# HorusBoard.net
KiCad netlist of a schematic drawn in EAGLE
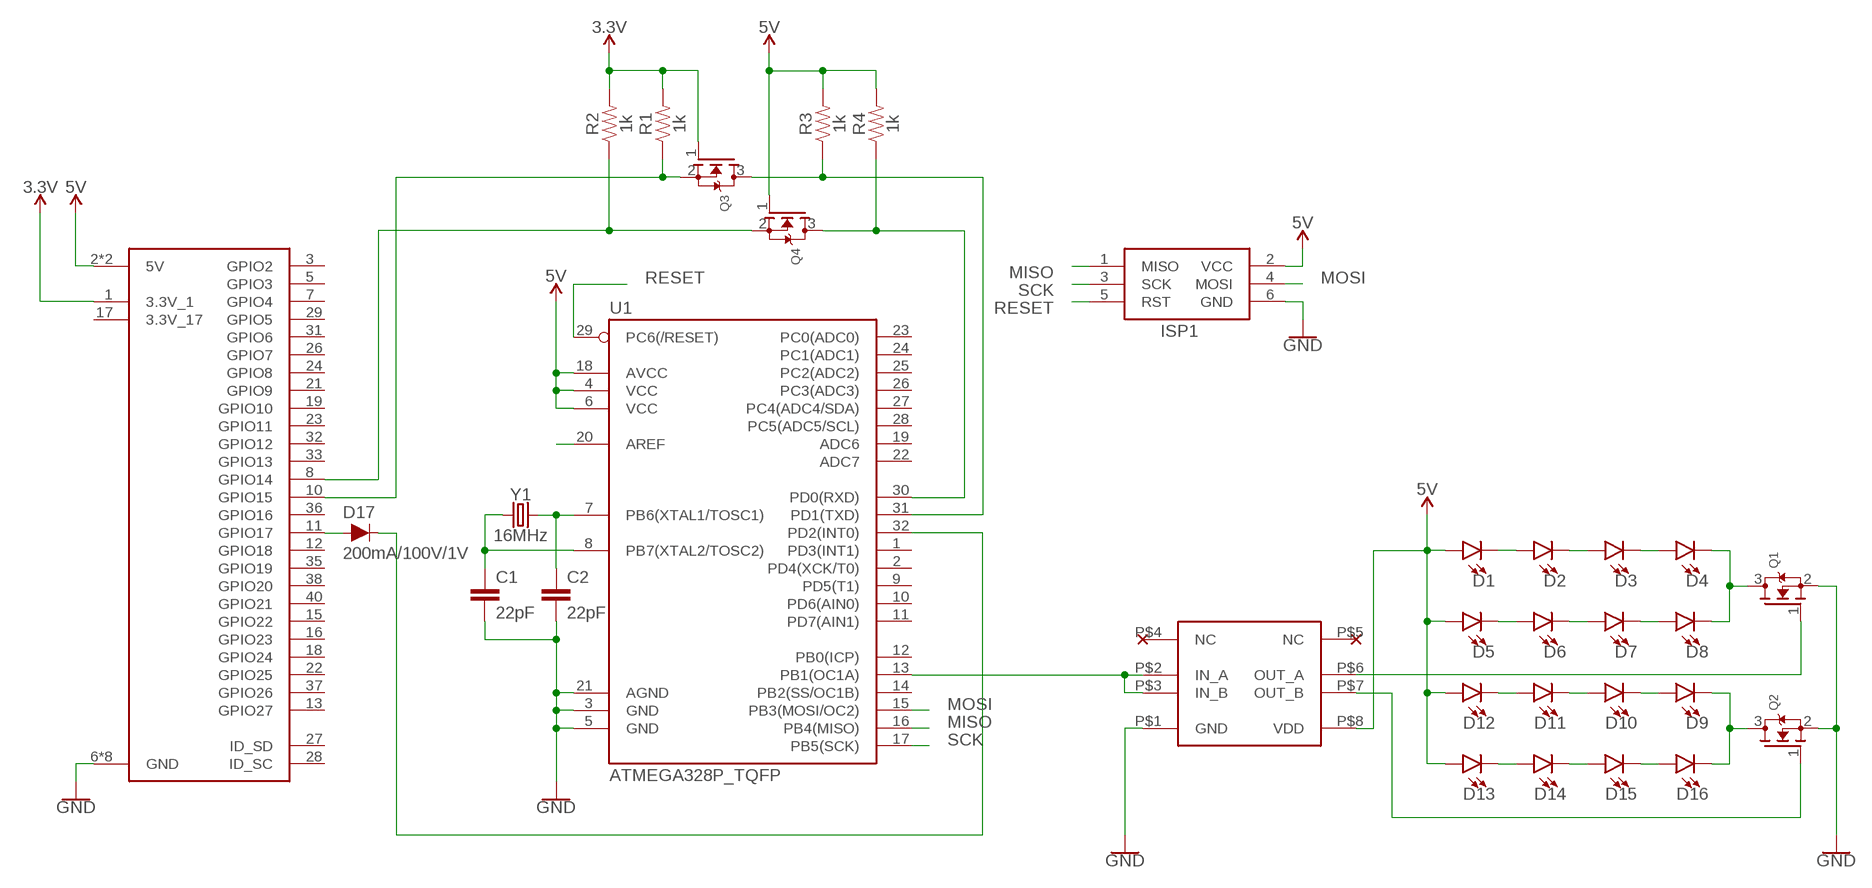
[diagram p0: schematic, sheet 1]

(export (version "E")
  (design (tool "Eeschema 10.0.6"))
  (components
    (comp (ref "C1")
      (value "22pF")
      (footprint "eagle-import:0603")
      (libsource (lib "eagle-import") (part "22PF-0603-50V-5%"))
    )
    (comp (ref "C2")
      (value "22pF")
      (footprint "eagle-import:0603")
      (libsource (lib "eagle-import") (part "22PF-0603-50V-5%"))
    )
    (comp (ref "D1")
      (value "LED3MM")
      (footprint "eagle-import:LED_3MM")
      (libsource (lib "eagle-import") (part "LED3MM"))
    )
    (comp (ref "D2")
      (value "LED3MM")
      (footprint "eagle-import:LED_3MM")
      (libsource (lib "eagle-import") (part "LED3MM"))
    )
    (comp (ref "D3")
      (value "LED3MM")
      (footprint "eagle-import:LED_3MM")
      (libsource (lib "eagle-import") (part "LED3MM"))
    )
    (comp (ref "D4")
      (value "LED3MM")
      (footprint "eagle-import:LED_3MM")
      (libsource (lib "eagle-import") (part "LED3MM"))
    )
    (comp (ref "D5")
      (value "LED3MM")
      (footprint "eagle-import:LED_3MM")
      (libsource (lib "eagle-import") (part "LED3MM"))
    )
    (comp (ref "D6")
      (value "LED3MM")
      (footprint "eagle-import:LED_3MM")
      (libsource (lib "eagle-import") (part "LED3MM"))
    )
    (comp (ref "D7")
      (value "LED3MM")
      (footprint "eagle-import:LED_3MM")
      (libsource (lib "eagle-import") (part "LED3MM"))
    )
    (comp (ref "D8")
      (value "LED3MM")
      (footprint "eagle-import:LED_3MM")
      (libsource (lib "eagle-import") (part "LED3MM"))
    )
    (comp (ref "D9")
      (value "LED3MM")
      (footprint "eagle-import:LED_3MM")
      (libsource (lib "eagle-import") (part "LED3MM"))
    )
    (comp (ref "D10")
      (value "LED3MM")
      (footprint "eagle-import:LED_3MM")
      (libsource (lib "eagle-import") (part "LED3MM"))
    )
    (comp (ref "D11")
      (value "LED3MM")
      (footprint "eagle-import:LED_3MM")
      (libsource (lib "eagle-import") (part "LED3MM"))
    )
    (comp (ref "D12")
      (value "LED3MM")
      (footprint "eagle-import:LED_3MM")
      (libsource (lib "eagle-import") (part "LED3MM"))
    )
    (comp (ref "D13")
      (value "LED3MM")
      (footprint "eagle-import:LED_3MM")
      (libsource (lib "eagle-import") (part "LED3MM"))
    )
    (comp (ref "D14")
      (value "LED3MM")
      (footprint "eagle-import:LED_3MM")
      (libsource (lib "eagle-import") (part "LED3MM"))
    )
    (comp (ref "D15")
      (value "LED3MM")
      (footprint "eagle-import:LED_3MM")
      (libsource (lib "eagle-import") (part "LED3MM"))
    )
    (comp (ref "D16")
      (value "LED3MM")
      (footprint "eagle-import:LED_3MM")
      (libsource (lib "eagle-import") (part "LED3MM"))
    )
    (comp (ref "D17")
      (value "200mA/100V/1V")
      (footprint "eagle-import:DIODE-1N4148")
      (libsource (lib "eagle-import") (part "DIODE-1N4148"))
    )
    (comp (ref "ISP1")
      (value "AVRISP-6")
      (footprint "eagle-import:AVRISP")
      (libsource (lib "eagle-import") (part "AVRISP-6"))
    )
    (comp (ref "Q1")
      (value "MOSFET-NREFLOW")
      (footprint "eagle-import:SOT23")
      (libsource (lib "eagle-import") (part "MOSFET-NREFLOW"))
    )
    (comp (ref "Q2")
      (value "MOSFET-NREFLOW")
      (footprint "eagle-import:SOT23")
      (libsource (lib "eagle-import") (part "MOSFET-NREFLOW"))
    )
    (comp (ref "Q3")
      (value "MOSFET-NREFLOW")
      (footprint "eagle-import:SOT23")
      (libsource (lib "eagle-import") (part "MOSFET-NREFLOW"))
    )
    (comp (ref "Q4")
      (value "MOSFET-NREFLOW")
      (footprint "eagle-import:SOT23")
      (libsource (lib "eagle-import") (part "MOSFET-NREFLOW"))
    )
    (comp (ref "R1")
      (value "1k")
      (footprint "eagle-import:AXIAL-0.3")
      (libsource (lib "eagle-import") (part "1KOHM-HORIZ-1/4W-5%"))
    )
    (comp (ref "R2")
      (value "1k")
      (footprint "eagle-import:AXIAL-0.3")
      (libsource (lib "eagle-import") (part "1KOHM-HORIZ-1/4W-5%"))
    )
    (comp (ref "R3")
      (value "1k")
      (footprint "eagle-import:AXIAL-0.3")
      (libsource (lib "eagle-import") (part "1KOHM-HORIZ-1/4W-5%"))
    )
    (comp (ref "R4")
      (value "1k")
      (footprint "eagle-import:AXIAL-0.3")
      (libsource (lib "eagle-import") (part "1KOHM-HORIZ-1/4W-5%"))
    )
    (comp (ref "U$1")
      (value "TC4427")
      (footprint "eagle-import:8-SOIC")
      (libsource (lib "eagle-import") (part "TC4427"))
    )
    (comp (ref "U$2")
      (value "RASPBERRY_PI_3")
      (footprint "eagle-import:RASPBERRY_PI_3")
      (libsource (lib "eagle-import") (part "RASPBERRY_PI_3"))
    )
    (comp (ref "U1")
      (value "ATMEGA328P_TQFP")
      (footprint "eagle-import:TQFP32-08")
      (libsource (lib "eagle-import") (part "ATMEGA328P_TQFP"))
    )
    (comp (ref "Y1")
      (value "16MHz")
      (footprint "eagle-import:HC49US")
      (libsource (lib "eagle-import") (part "CRYSTAL-16MHZPTH-HC49US"))
    )
  )
  (nets
    (net (code "1") (name "/MISO") (class "Default")
      (node (ref "ISP1") (pin "1") (pinfunction "MISO_1") (pintype "input"))
      (node (ref "U1") (pin "16") (pinfunction "PB4(MISO)_16") (pintype "bidirectional"))
    )
    (net (code "2") (name "/MOSI") (class "Default")
      (node (ref "ISP1") (pin "4") (pinfunction "MOSI_4") (pintype "output"))
      (node (ref "U1") (pin "15") (pinfunction "PB3(MOSI/OC2)_15") (pintype "bidirectional"))
    )
    (net (code "3") (name "/RESET") (class "Default")
      (node (ref "ISP1") (pin "5") (pinfunction "RST_5") (pintype "output"))
      (node (ref "U1") (pin "29") (pinfunction "PC6(/RESET)_29") (pintype "bidirectional"))
    )
    (net (code "4") (name "/SCK") (class "Default")
      (node (ref "ISP1") (pin "3") (pinfunction "SCK_3") (pintype "output"))
      (node (ref "U1") (pin "17") (pinfunction "PB5(SCK)_17") (pintype "bidirectional"))
    )
    (net (code "5") (name "3.3V") (class "Default")
      (node (ref "Q3") (pin "1") (pinfunction "G_1") (pintype "bidirectional"))
      (node (ref "R1") (pin "P$2") (pinfunction "2_P$2") (pintype "passive"))
      (node (ref "R2") (pin "P$2") (pinfunction "2_P$2") (pintype "passive"))
      (node (ref "U$2") (pin "1") (pinfunction "3.3V_1_1") (pintype "bidirectional"))
    )
    (net (code "6") (name "5V") (class "Default")
      (node (ref "D1") (pin "A") (pinfunction "A_A") (pintype "passive"))
      (node (ref "D12") (pin "A") (pinfunction "A_A") (pintype "passive"))
      (node (ref "D13") (pin "A") (pinfunction "A_A") (pintype "passive"))
      (node (ref "D5") (pin "A") (pinfunction "A_A") (pintype "passive"))
      (node (ref "ISP1") (pin "2") (pinfunction "VCC_2") (pintype "power_in"))
      (node (ref "Q4") (pin "1") (pinfunction "G_1") (pintype "bidirectional"))
      (node (ref "R3") (pin "P$2") (pinfunction "2_P$2") (pintype "passive"))
      (node (ref "R4") (pin "P$2") (pinfunction "2_P$2") (pintype "passive"))
      (node (ref "U$1") (pin "P$8") (pinfunction "VDD_P$8") (pintype "bidirectional"))
      (node (ref "U$2") (pin "2") (pinfunction "5V_2") (pintype "bidirectional"))
      (node (ref "U$2") (pin "4") (pinfunction "5V_4") (pintype "bidirectional"))
      (node (ref "U1") (pin "18") (pinfunction "AVCC_18") (pintype "bidirectional"))
      (node (ref "U1") (pin "4") (pinfunction "VCC_4") (pintype "bidirectional"))
      (node (ref "U1") (pin "6") (pinfunction "VCC_6") (pintype "bidirectional"))
    )
    (net (code "7") (name "GND") (class "Default")
      (node (ref "C1") (pin "2") (pinfunction "2_2") (pintype "passive"))
      (node (ref "C2") (pin "2") (pinfunction "2_2") (pintype "passive"))
      (node (ref "ISP1") (pin "6") (pinfunction "GND_6") (pintype "power_in"))
      (node (ref "Q1") (pin "2") (pinfunction "S_2") (pintype "bidirectional"))
      (node (ref "Q2") (pin "2") (pinfunction "S_2") (pintype "bidirectional"))
      (node (ref "U$1") (pin "P$1") (pinfunction "GND_P$1") (pintype "bidirectional"))
      (node (ref "U$2") (pin "14") (pinfunction "GND_14") (pintype "bidirectional"))
      (node (ref "U$2") (pin "20") (pinfunction "GND_20") (pintype "bidirectional"))
      (node (ref "U$2") (pin "25") (pinfunction "GND_25") (pintype "bidirectional"))
      (node (ref "U$2") (pin "30") (pinfunction "GND_30") (pintype "bidirectional"))
      (node (ref "U$2") (pin "34") (pinfunction "GND_34") (pintype "bidirectional"))
      (node (ref "U$2") (pin "39") (pinfunction "GND_39") (pintype "bidirectional"))
      (node (ref "U$2") (pin "6") (pinfunction "GND_6") (pintype "bidirectional"))
      (node (ref "U$2") (pin "9") (pinfunction "GND_9") (pintype "bidirectional"))
      (node (ref "U1") (pin "21") (pinfunction "AGND_21") (pintype "bidirectional"))
      (node (ref "U1") (pin "3") (pinfunction "GND_3") (pintype "bidirectional"))
      (node (ref "U1") (pin "5") (pinfunction "GND_5") (pintype "bidirectional"))
    )
    (net (code "8") (name "Net-(D1-C)") (class "Default")
      (node (ref "D1") (pin "K") (pinfunction "C_K") (pintype "passive"))
      (node (ref "D2") (pin "A") (pinfunction "A_A") (pintype "passive"))
    )
    (net (code "9") (name "Net-(D2-C)") (class "Default")
      (node (ref "D2") (pin "K") (pinfunction "C_K") (pintype "passive"))
      (node (ref "D3") (pin "A") (pinfunction "A_A") (pintype "passive"))
    )
    (net (code "10") (name "Net-(D3-C)") (class "Default")
      (node (ref "D3") (pin "K") (pinfunction "C_K") (pintype "passive"))
      (node (ref "D4") (pin "A") (pinfunction "A_A") (pintype "passive"))
    )
    (net (code "11") (name "Net-(D4-C)") (class "Default")
      (node (ref "D4") (pin "K") (pinfunction "C_K") (pintype "passive"))
      (node (ref "D8") (pin "K") (pinfunction "C_K") (pintype "passive"))
      (node (ref "Q1") (pin "3") (pinfunction "D_3") (pintype "bidirectional"))
    )
    (net (code "12") (name "Net-(D5-C)") (class "Default")
      (node (ref "D5") (pin "K") (pinfunction "C_K") (pintype "passive"))
      (node (ref "D6") (pin "A") (pinfunction "A_A") (pintype "passive"))
    )
    (net (code "13") (name "Net-(D6-C)") (class "Default")
      (node (ref "D6") (pin "K") (pinfunction "C_K") (pintype "passive"))
      (node (ref "D7") (pin "A") (pinfunction "A_A") (pintype "passive"))
    )
    (net (code "14") (name "Net-(D7-C)") (class "Default")
      (node (ref "D7") (pin "K") (pinfunction "C_K") (pintype "passive"))
      (node (ref "D8") (pin "A") (pinfunction "A_A") (pintype "passive"))
    )
    (net (code "15") (name "Net-(D10-C)") (class "Default")
      (node (ref "D10") (pin "K") (pinfunction "C_K") (pintype "passive"))
      (node (ref "D9") (pin "A") (pinfunction "A_A") (pintype "passive"))
    )
    (net (code "16") (name "Net-(D11-C)") (class "Default")
      (node (ref "D10") (pin "A") (pinfunction "A_A") (pintype "passive"))
      (node (ref "D11") (pin "K") (pinfunction "C_K") (pintype "passive"))
    )
    (net (code "17") (name "Net-(D12-C)") (class "Default")
      (node (ref "D11") (pin "A") (pinfunction "A_A") (pintype "passive"))
      (node (ref "D12") (pin "K") (pinfunction "C_K") (pintype "passive"))
    )
    (net (code "18") (name "Net-(D13-C)") (class "Default")
      (node (ref "D13") (pin "K") (pinfunction "C_K") (pintype "passive"))
      (node (ref "D14") (pin "A") (pinfunction "A_A") (pintype "passive"))
    )
    (net (code "19") (name "Net-(D14-C)") (class "Default")
      (node (ref "D14") (pin "K") (pinfunction "C_K") (pintype "passive"))
      (node (ref "D15") (pin "A") (pinfunction "A_A") (pintype "passive"))
    )
    (net (code "20") (name "Net-(D15-C)") (class "Default")
      (node (ref "D15") (pin "K") (pinfunction "C_K") (pintype "passive"))
      (node (ref "D16") (pin "A") (pinfunction "A_A") (pintype "passive"))
    )
    (net (code "21") (name "Net-(D16-C)") (class "Default")
      (node (ref "D16") (pin "K") (pinfunction "C_K") (pintype "passive"))
      (node (ref "D9") (pin "K") (pinfunction "C_K") (pintype "passive"))
      (node (ref "Q2") (pin "3") (pinfunction "D_3") (pintype "bidirectional"))
    )
    (net (code "22") (name "Net-(Q1-G)") (class "Default")
      (node (ref "Q1") (pin "1") (pinfunction "G_1") (pintype "bidirectional"))
      (node (ref "U$1") (pin "P$6") (pinfunction "OUT_A_P$6") (pintype "bidirectional"))
    )
    (net (code "23") (name "Net-(Q2-G)") (class "Default")
      (node (ref "Q2") (pin "1") (pinfunction "G_1") (pintype "bidirectional"))
      (node (ref "U$1") (pin "P$7") (pinfunction "OUT_B_P$7") (pintype "bidirectional"))
    )
    (net (code "24") (name "Net-(Q3-D)") (class "Default")
      (node (ref "Q3") (pin "3") (pinfunction "D_3") (pintype "bidirectional"))
      (node (ref "R3") (pin "P$1") (pinfunction "1_P$1") (pintype "passive"))
      (node (ref "U1") (pin "31") (pinfunction "PD1(TXD)_31") (pintype "bidirectional"))
    )
    (net (code "25") (name "Net-(Q3-S)") (class "Default")
      (node (ref "Q3") (pin "2") (pinfunction "S_2") (pintype "bidirectional"))
      (node (ref "R1") (pin "P$1") (pinfunction "1_P$1") (pintype "passive"))
      (node (ref "U$2") (pin "10") (pinfunction "GPIO15_10") (pintype "bidirectional"))
    )
    (net (code "26") (name "Net-(Q4-D)") (class "Default")
      (node (ref "Q4") (pin "3") (pinfunction "D_3") (pintype "bidirectional"))
      (node (ref "R4") (pin "P$1") (pinfunction "1_P$1") (pintype "passive"))
      (node (ref "U1") (pin "30") (pinfunction "PD0(RXD)_30") (pintype "bidirectional"))
    )
    (net (code "27") (name "Net-(Q4-S)") (class "Default")
      (node (ref "Q4") (pin "2") (pinfunction "S_2") (pintype "bidirectional"))
      (node (ref "R2") (pin "P$1") (pinfunction "1_P$1") (pintype "passive"))
      (node (ref "U$2") (pin "8") (pinfunction "GPIO14_8") (pintype "bidirectional"))
    )
    (net (code "28") (name "Net-(U$1-IN_A)") (class "Default")
      (node (ref "U$1") (pin "P$2") (pinfunction "IN_A_P$2") (pintype "bidirectional"))
      (node (ref "U$1") (pin "P$3") (pinfunction "IN_B_P$3") (pintype "bidirectional"))
      (node (ref "U1") (pin "13") (pinfunction "PB1(OC1A)_13") (pintype "bidirectional"))
    )
    (net (code "29") (name "Net-(U$2-GPIO17)") (class "Default")
      (node (ref "D17") (pin "A") (pinfunction "A_A") (pintype "passive"))
      (node (ref "U$2") (pin "11") (pinfunction "GPIO17_11") (pintype "bidirectional"))
    )
    (net (code "30") (name "Net-(U1-PB6(XTAL1{slash}TOSC1))") (class "Default")
      (node (ref "C2") (pin "1") (pinfunction "1_1") (pintype "passive"))
      (node (ref "U1") (pin "7") (pinfunction "PB6(XTAL1/TOSC1)_7") (pintype "bidirectional"))
      (node (ref "Y1") (pin "2") (pinfunction "2_2") (pintype "passive"))
    )
    (net (code "31") (name "Net-(U1-PB7(XTAL2{slash}TOSC2))") (class "Default")
      (node (ref "C1") (pin "1") (pinfunction "1_1") (pintype "passive"))
      (node (ref "U1") (pin "8") (pinfunction "PB7(XTAL2/TOSC2)_8") (pintype "bidirectional"))
      (node (ref "Y1") (pin "1") (pinfunction "1_1") (pintype "passive"))
    )
    (net (code "32") (name "Net-(U1-PD2(INT0))") (class "Default")
      (node (ref "D17") (pin "C") (pinfunction "C_C") (pintype "passive"))
      (node (ref "U1") (pin "32") (pinfunction "PD2(INT0)_32") (pintype "bidirectional"))
    )
    (net (code "33") (name "unconnected-(U$1-NC-PadP$4)") (class "Default")
      (node (ref "U$1") (pin "P$4") (pinfunction "NC_P$4") (pintype "no_connect"))
    )
    (net (code "34") (name "unconnected-(U$1-NC-PadP$5)") (class "Default")
      (node (ref "U$1") (pin "P$5") (pinfunction "NC_P$5") (pintype "no_connect"))
    )
    (net (code "35") (name "unconnected-(U$2-3.3V_17-Pad17)") (class "Default")
      (node (ref "U$2") (pin "17") (pinfunction "3.3V_17_17") (pintype "bidirectional"))
    )
    (net (code "36") (name "unconnected-(U$2-GPIO2-Pad3)") (class "Default")
      (node (ref "U$2") (pin "3") (pinfunction "GPIO2_3") (pintype "bidirectional"))
    )
    (net (code "37") (name "unconnected-(U$2-GPIO3-Pad5)") (class "Default")
      (node (ref "U$2") (pin "5") (pinfunction "GPIO3_5") (pintype "bidirectional"))
    )
    (net (code "38") (name "unconnected-(U$2-GPIO4-Pad7)") (class "Default")
      (node (ref "U$2") (pin "7") (pinfunction "GPIO4_7") (pintype "bidirectional"))
    )
    (net (code "39") (name "unconnected-(U$2-GPIO5-Pad29)") (class "Default")
      (node (ref "U$2") (pin "29") (pinfunction "GPIO5_29") (pintype "bidirectional"))
    )
    (net (code "40") (name "unconnected-(U$2-GPIO6-Pad31)") (class "Default")
      (node (ref "U$2") (pin "31") (pinfunction "GPIO6_31") (pintype "bidirectional"))
    )
    (net (code "41") (name "unconnected-(U$2-GPIO7-Pad26)") (class "Default")
      (node (ref "U$2") (pin "26") (pinfunction "GPIO7_26") (pintype "bidirectional"))
    )
    (net (code "42") (name "unconnected-(U$2-GPIO8-Pad24)") (class "Default")
      (node (ref "U$2") (pin "24") (pinfunction "GPIO8_24") (pintype "bidirectional"))
    )
    (net (code "43") (name "unconnected-(U$2-GPIO9-Pad21)") (class "Default")
      (node (ref "U$2") (pin "21") (pinfunction "GPIO9_21") (pintype "bidirectional"))
    )
    (net (code "44") (name "unconnected-(U$2-GPIO10-Pad19)") (class "Default")
      (node (ref "U$2") (pin "19") (pinfunction "GPIO10_19") (pintype "bidirectional"))
    )
    (net (code "45") (name "unconnected-(U$2-GPIO11-Pad23)") (class "Default")
      (node (ref "U$2") (pin "23") (pinfunction "GPIO11_23") (pintype "bidirectional"))
    )
    (net (code "46") (name "unconnected-(U$2-GPIO12-Pad32)") (class "Default")
      (node (ref "U$2") (pin "32") (pinfunction "GPIO12_32") (pintype "bidirectional"))
    )
    (net (code "47") (name "unconnected-(U$2-GPIO13-Pad33)") (class "Default")
      (node (ref "U$2") (pin "33") (pinfunction "GPIO13_33") (pintype "bidirectional"))
    )
    (net (code "48") (name "unconnected-(U$2-GPIO16-Pad36)") (class "Default")
      (node (ref "U$2") (pin "36") (pinfunction "GPIO16_36") (pintype "bidirectional"))
    )
    (net (code "49") (name "unconnected-(U$2-GPIO18-Pad12)") (class "Default")
      (node (ref "U$2") (pin "12") (pinfunction "GPIO18_12") (pintype "bidirectional"))
    )
    (net (code "50") (name "unconnected-(U$2-GPIO19-Pad35)") (class "Default")
      (node (ref "U$2") (pin "35") (pinfunction "GPIO19_35") (pintype "bidirectional"))
    )
    (net (code "51") (name "unconnected-(U$2-GPIO20-Pad38)") (class "Default")
      (node (ref "U$2") (pin "38") (pinfunction "GPIO20_38") (pintype "bidirectional"))
    )
    (net (code "52") (name "unconnected-(U$2-GPIO21-Pad40)") (class "Default")
      (node (ref "U$2") (pin "40") (pinfunction "GPIO21_40") (pintype "bidirectional"))
    )
    (net (code "53") (name "unconnected-(U$2-GPIO22-Pad15)") (class "Default")
      (node (ref "U$2") (pin "15") (pinfunction "GPIO22_15") (pintype "bidirectional"))
    )
    (net (code "54") (name "unconnected-(U$2-GPIO23-Pad16)") (class "Default")
      (node (ref "U$2") (pin "16") (pinfunction "GPIO23_16") (pintype "bidirectional"))
    )
    (net (code "55") (name "unconnected-(U$2-GPIO24-Pad18)") (class "Default")
      (node (ref "U$2") (pin "18") (pinfunction "GPIO24_18") (pintype "bidirectional"))
    )
    (net (code "56") (name "unconnected-(U$2-GPIO25-Pad22)") (class "Default")
      (node (ref "U$2") (pin "22") (pinfunction "GPIO25_22") (pintype "bidirectional"))
    )
    (net (code "57") (name "unconnected-(U$2-GPIO26-Pad37)") (class "Default")
      (node (ref "U$2") (pin "37") (pinfunction "GPIO26_37") (pintype "bidirectional"))
    )
    (net (code "58") (name "unconnected-(U$2-GPIO27-Pad13)") (class "Default")
      (node (ref "U$2") (pin "13") (pinfunction "GPIO27_13") (pintype "bidirectional"))
    )
    (net (code "59") (name "unconnected-(U$2-ID_SC-Pad28)") (class "Default")
      (node (ref "U$2") (pin "28") (pinfunction "ID_SC_28") (pintype "bidirectional"))
    )
    (net (code "60") (name "unconnected-(U$2-ID_SD-Pad27)") (class "Default")
      (node (ref "U$2") (pin "27") (pinfunction "ID_SD_27") (pintype "bidirectional"))
    )
    (net (code "61") (name "unconnected-(U1-ADC6-Pad19)") (class "Default")
      (node (ref "U1") (pin "19") (pinfunction "ADC6_19") (pintype "bidirectional"))
    )
    (net (code "62") (name "unconnected-(U1-ADC7-Pad22)") (class "Default")
      (node (ref "U1") (pin "22") (pinfunction "ADC7_22") (pintype "bidirectional"))
    )
    (net (code "63") (name "unconnected-(U1-AREF-Pad20)") (class "Default")
      (node (ref "U1") (pin "20") (pinfunction "AREF_20") (pintype "bidirectional"))
    )
    (net (code "64") (name "unconnected-(U1-PB0(ICP)-Pad12)") (class "Default")
      (node (ref "U1") (pin "12") (pinfunction "PB0(ICP)_12") (pintype "bidirectional"))
    )
    (net (code "65") (name "unconnected-(U1-PB2(SS{slash}OC1B)-Pad14)") (class "Default")
      (node (ref "U1") (pin "14") (pinfunction "PB2(SS/OC1B)_14") (pintype "bidirectional"))
    )
    (net (code "66") (name "unconnected-(U1-PC0(ADC0)-Pad23)") (class "Default")
      (node (ref "U1") (pin "23") (pinfunction "PC0(ADC0)_23") (pintype "bidirectional"))
    )
    (net (code "67") (name "unconnected-(U1-PC1(ADC1)-Pad24)") (class "Default")
      (node (ref "U1") (pin "24") (pinfunction "PC1(ADC1)_24") (pintype "bidirectional"))
    )
    (net (code "68") (name "unconnected-(U1-PC2(ADC2)-Pad25)") (class "Default")
      (node (ref "U1") (pin "25") (pinfunction "PC2(ADC2)_25") (pintype "bidirectional"))
    )
    (net (code "69") (name "unconnected-(U1-PC3(ADC3)-Pad26)") (class "Default")
      (node (ref "U1") (pin "26") (pinfunction "PC3(ADC3)_26") (pintype "bidirectional"))
    )
    (net (code "70") (name "unconnected-(U1-PC4(ADC4{slash}SDA)-Pad27)") (class "Default")
      (node (ref "U1") (pin "27") (pinfunction "PC4(ADC4/SDA)_27") (pintype "bidirectional"))
    )
    (net (code "71") (name "unconnected-(U1-PC5(ADC5{slash}SCL)-Pad28)") (class "Default")
      (node (ref "U1") (pin "28") (pinfunction "PC5(ADC5/SCL)_28") (pintype "bidirectional"))
    )
    (net (code "72") (name "unconnected-(U1-PD3(INT1)-Pad1)") (class "Default")
      (node (ref "U1") (pin "1") (pinfunction "PD3(INT1)_1") (pintype "bidirectional"))
    )
    (net (code "73") (name "unconnected-(U1-PD4(XCK{slash}T0)-Pad2)") (class "Default")
      (node (ref "U1") (pin "2") (pinfunction "PD4(XCK/T0)_2") (pintype "bidirectional"))
    )
    (net (code "74") (name "unconnected-(U1-PD5(T1)-Pad9)") (class "Default")
      (node (ref "U1") (pin "9") (pinfunction "PD5(T1)_9") (pintype "bidirectional"))
    )
    (net (code "75") (name "unconnected-(U1-PD6(AIN0)-Pad10)") (class "Default")
      (node (ref "U1") (pin "10") (pinfunction "PD6(AIN0)_10") (pintype "bidirectional"))
    )
    (net (code "76") (name "unconnected-(U1-PD7(AIN1)-Pad11)") (class "Default")
      (node (ref "U1") (pin "11") (pinfunction "PD7(AIN1)_11") (pintype "bidirectional"))
    )
  )
)
